# MCPS_Power_030414.net
KiCad netlist of a schematic drawn in Altium Designer
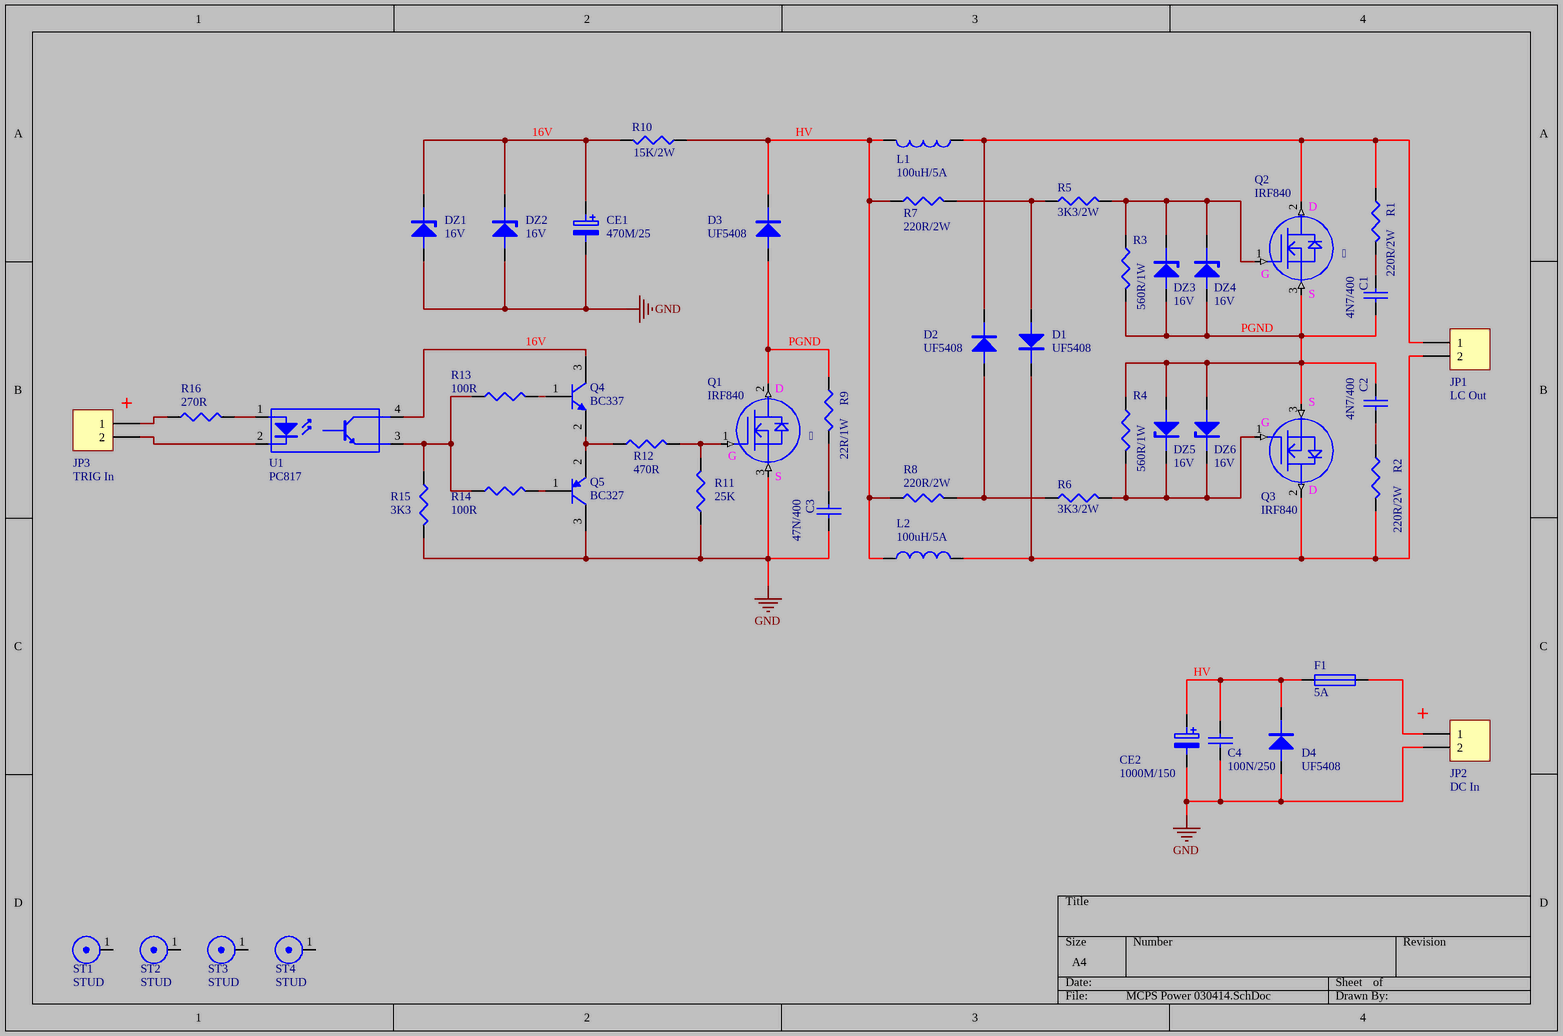
[diagram p0: MCPS Power 030414.SchDoc]

(export (version "E")
  (design (tool "Eeschema 10.0.6"))
  (components
    (comp (ref "C1") (value "4N7/400") (footprint "C3P") (libsource (lib "*") (part "C")))
    (comp (ref "C2") (value "4N7/400") (footprint "C3P") (libsource (lib "*") (part "C")))
    (comp (ref "C3") (value "47N/400") (footprint "C2P") (libsource (lib "*") (part "C")))
    (comp (ref "C4") (value "100N/250") (footprint "C4P") (libsource (lib "*") (part "C")))
    (comp (ref "CE1") (value "470M/25") (footprint "cap2p12") (libsource (lib "*") (part "E")))
    (comp (ref "CE2") (value "1000M/150") (footprint "CAP3P5") (libsource (lib "*") (part "E")))
    (comp (ref "D1") (value "UF5408") (footprint "D54") (libsource (lib "MyAltiumLib9702") (part "D")))
    (comp (ref "D2") (value "UF5408") (footprint "D54") (libsource (lib "MyAltiumLib9702") (part "D")))
    (comp (ref "D3") (value "UF5408") (footprint "D54") (libsource (lib "MyAltiumLib9702") (part "D")))
    (comp (ref "D4") (value "UF5408") (footprint "D54") (libsource (lib "MyAltiumLib9702") (part "D")))
    (comp (ref "DZ1") (value "16V") (footprint "D5P") (libsource (lib "MyAltiumLib9702") (part "DZ")))
    (comp (ref "DZ2") (value "16V") (footprint "D5P") (libsource (lib "MyAltiumLib9702") (part "DZ")))
    (comp (ref "DZ3") (value "16V") (footprint "D5P") (libsource (lib "MyAltiumLib9702") (part "DZ")))
    (comp (ref "DZ4") (value "16V") (footprint "D5P") (libsource (lib "MyAltiumLib9702") (part "DZ")))
    (comp (ref "DZ5") (value "16V") (footprint "D5P") (libsource (lib "MyAltiumLib9702") (part "DZ")))
    (comp (ref "DZ6") (value "16V") (footprint "D5P") (libsource (lib "MyAltiumLib9702") (part "DZ")))
    (comp (ref "F1") (value "5A") (footprint "FS") (libsource (lib "1402 Schlib 2020") (part "FUSE1")))
    (comp (ref "JP1")
      (value "LC Out")
      (footprint "DG55X2")
      (description "Header, 2-Pin")
      (fields (field (name "PUBLISHER") "Altium Limited"))
      (libsource (lib "Miscellaneous Connectors") (part "Header 2"))
    )
    (comp (ref "JP2")
      (value "DC In")
      (footprint "DG55X2")
      (description "Header, 2-Pin")
      (fields (field (name "PUBLISHER") "Altium Limited"))
      (libsource (lib "Miscellaneous Connectors") (part "Header 2"))
    )
    (comp (ref "JP3")
      (value "TRIG In")
      (footprint "DSIP2")
      (description "Header, 2-Pin")
      (fields (field (name "PUBLISHER") "Altium Limited"))
      (libsource (lib "") (part "Header 2_1"))
    )
    (comp (ref "L1") (value "100uH/5A") (footprint "Inductor3916") (libsource (lib "") (part "INDUCTOR_1")))
    (comp (ref "L2")
      (value "100uH/5A")
      (footprint "Inductor3916")
      (libsource (lib "MyAltiumLib9702") (part "INDUCTOR"))
    )
    (comp (ref "Q1")
      (value "")
      (footprint "TO247-MOSPIN")
      (libsource (lib "1402 Schlib 2020") (part "MOSFET N"))
    )
    (comp (ref "Q2")
      (value "")
      (footprint "TO247-MOSPIN")
      (libsource (lib "1402 Schlib 2020") (part "MOSFET N"))
    )
    (comp (ref "Q3")
      (value "IRF840")
      (footprint "TO247-MOSPIN")
      (libsource (lib "1402 Schlib 2020") (part "MOSFET N"))
    )
    (comp (ref "Q4")
      (value "BC337")
      (footprint "CBE-BC546")
      (libsource (lib "1402 Schlib 2020") (part "BC546"))
    )
    (comp (ref "Q5")
      (value "BC327")
      (footprint "CBE-BC546")
      (description "PNP")
      (fields (field (name "PUBLISHER") "Altium Limited"))
      (libsource (lib "1402 Schlib 2020") (part "M6"))
    )
    (comp (ref "R1") (value "220R/2W") (footprint "W2") (libsource (lib "*") (part "R")))
    (comp (ref "R2") (value "220R/2W") (footprint "W2") (libsource (lib "*") (part "R")))
    (comp (ref "R3") (value "560R/1W") (footprint "W1") (libsource (lib "*") (part "R")))
    (comp (ref "R4") (value "560R/1W") (footprint "W1") (libsource (lib "*") (part "R")))
    (comp (ref "R5") (value "3K3/2W") (footprint "W2") (libsource (lib "*") (part "R")))
    (comp (ref "R6") (value "3K3/2W") (footprint "W2") (libsource (lib "*") (part "R")))
    (comp (ref "R7") (value "220R/2W") (footprint "W2") (libsource (lib "*") (part "R")))
    (comp (ref "R8") (value "220R/2W") (footprint "W2") (libsource (lib "*") (part "R")))
    (comp (ref "R9") (value "22R/1W") (footprint "W1") (libsource (lib "*") (part "R")))
    (comp (ref "R10") (value "15K/2W") (footprint "W2") (libsource (lib "*") (part "R")))
    (comp (ref "R11") (value "25K") (footprint "W1/4") (libsource (lib "*") (part "R")))
    (comp (ref "R12") (value "470R") (footprint "W1/4") (libsource (lib "*") (part "R")))
    (comp (ref "R13") (value "100R") (footprint "W1/4") (libsource (lib "*") (part "R")))
    (comp (ref "R14") (value "100R") (footprint "W1/4") (libsource (lib "*") (part "R")))
    (comp (ref "R15") (value "3K3") (footprint "W1/4") (libsource (lib "*") (part "R")))
    (comp (ref "R16") (value "270R") (footprint "W1/4") (libsource (lib "*") (part "R")))
    (comp (ref "ST1") (value "STUD") (footprint "CORNER") (libsource (lib "1402 Schlib 2020") (part "STUD")))
    (comp (ref "ST2") (value "STUD") (footprint "CORNER") (libsource (lib "1402 Schlib 2020") (part "STUD")))
    (comp (ref "ST3") (value "STUD") (footprint "CORNER") (libsource (lib "1402 Schlib 2020") (part "STUD")))
    (comp (ref "ST4") (value "STUD") (footprint "CORNER") (libsource (lib "1402 Schlib 2020") (part "STUD")))
    (comp (ref "U1")
      (value "PC817")
      (footprint "DIP4")
      (libsource (lib "1402 Schlib 2020") (part "OPTODIP4"))
    )
  )
  (nets
    (net (code "1") (name "/16V") (class "Default")
      (node (ref "CE1") (pin "1") (pintype "passive"))
      (node (ref "DZ1") (pin "2") (pinfunction "K_2") (pintype "passive"))
      (node (ref "DZ2") (pin "2") (pinfunction "K_2") (pintype "passive"))
      (node (ref "Q4") (pin "3") (pinfunction "C_3") (pintype "passive"))
      (node (ref "R10") (pin "2") (pintype "passive"))
      (node (ref "U1") (pin "4") (pinfunction "C_4") (pintype "passive"))
    )
    (net (code "2") (name "/HV") (class "Default")
      (node (ref "C4") (pin "1") (pintype "passive"))
      (node (ref "CE2") (pin "1") (pintype "passive"))
      (node (ref "D3") (pin "2") (pinfunction "K_2") (pintype "passive"))
      (node (ref "D4") (pin "2") (pinfunction "K_2") (pintype "passive"))
      (node (ref "F1") (pin "1") (pintype "passive"))
      (node (ref "L1") (pin "1") (pinfunction "1_1") (pintype "passive"))
      (node (ref "L2") (pin "1") (pinfunction "1_1") (pintype "passive"))
      (node (ref "R10") (pin "1") (pintype "passive"))
      (node (ref "R7") (pin "1") (pintype "passive"))
      (node (ref "R8") (pin "1") (pintype "passive"))
    )
    (net (code "3") (name "/PGND") (class "Default")
      (node (ref "C1") (pin "2") (pintype "passive"))
      (node (ref "C2") (pin "2") (pintype "passive"))
      (node (ref "D3") (pin "1") (pinfunction "A_1") (pintype "passive"))
      (node (ref "DZ3") (pin "1") (pinfunction "A_1") (pintype "passive"))
      (node (ref "DZ4") (pin "1") (pinfunction "A_1") (pintype "passive"))
      (node (ref "DZ5") (pin "1") (pinfunction "A_1") (pintype "passive"))
      (node (ref "DZ6") (pin "1") (pinfunction "A_1") (pintype "passive"))
      (node (ref "Q1") (pin "2") (pinfunction "D_2") (pintype "output"))
      (node (ref "Q2") (pin "3") (pinfunction "S_3") (pintype "input"))
      (node (ref "Q3") (pin "3") (pinfunction "S_3") (pintype "input"))
      (node (ref "R3") (pin "2") (pintype "passive"))
      (node (ref "R4") (pin "1") (pintype "passive"))
      (node (ref "R9") (pin "1") (pintype "passive"))
    )
    (net (code "4") (name "GND") (class "Default")
      (node (ref "C3") (pin "2") (pintype "passive"))
      (node (ref "C4") (pin "2") (pintype "passive"))
      (node (ref "CE1") (pin "2") (pintype "passive"))
      (node (ref "CE2") (pin "2") (pintype "passive"))
      (node (ref "D4") (pin "1") (pinfunction "A_1") (pintype "passive"))
      (node (ref "DZ1") (pin "1") (pinfunction "A_1") (pintype "passive"))
      (node (ref "DZ2") (pin "1") (pinfunction "A_1") (pintype "passive"))
      (node (ref "JP2") (pin "2") (pinfunction "2_2") (pintype "passive"))
      (node (ref "Q1") (pin "3") (pinfunction "S_3") (pintype "input"))
      (node (ref "Q5") (pin "3") (pinfunction "C_3") (pintype "passive"))
      (node (ref "R11") (pin "1") (pintype "passive"))
      (node (ref "R15") (pin "2") (pintype "passive"))
    )
    (net (code "5") (name "Net-(C1-Pad1)") (class "Default")
      (node (ref "C1") (pin "1") (pintype "passive"))
      (node (ref "R1") (pin "2") (pintype "passive"))
    )
    (net (code "6") (name "Net-(C2-Pad1)") (class "Default")
      (node (ref "C2") (pin "1") (pintype "passive"))
      (node (ref "R2") (pin "2") (pintype "passive"))
    )
    (net (code "7") (name "Net-(C3-Pad1)") (class "Default")
      (node (ref "C3") (pin "1") (pintype "passive"))
      (node (ref "R9") (pin "2") (pintype "passive"))
    )
    (net (code "8") (name "Net-(D1-A)") (class "Default")
      (node (ref "D1") (pin "1") (pinfunction "A_1") (pintype "passive"))
      (node (ref "R5") (pin "1") (pintype "passive"))
      (node (ref "R7") (pin "2") (pintype "passive"))
    )
    (net (code "9") (name "Net-(D1-K)") (class "Default")
      (node (ref "D1") (pin "2") (pinfunction "K_2") (pintype "passive"))
      (node (ref "JP1") (pin "2") (pinfunction "2_2") (pintype "passive"))
      (node (ref "L2") (pin "2") (pinfunction "2_2") (pintype "passive"))
      (node (ref "Q3") (pin "2") (pinfunction "D_2") (pintype "output"))
      (node (ref "R2") (pin "1") (pintype "passive"))
    )
    (net (code "10") (name "Net-(D2-A)") (class "Default")
      (node (ref "D2") (pin "1") (pinfunction "A_1") (pintype "passive"))
      (node (ref "R6") (pin "1") (pintype "passive"))
      (node (ref "R8") (pin "2") (pintype "passive"))
    )
    (net (code "11") (name "Net-(D2-K)") (class "Default")
      (node (ref "D2") (pin "2") (pinfunction "K_2") (pintype "passive"))
      (node (ref "JP1") (pin "1") (pinfunction "1_1") (pintype "passive"))
      (node (ref "L1") (pin "2") (pinfunction "2_2") (pintype "passive"))
      (node (ref "Q2") (pin "2") (pinfunction "D_2") (pintype "output"))
      (node (ref "R1") (pin "1") (pintype "passive"))
    )
    (net (code "12") (name "Net-(DZ3-K)") (class "Default")
      (node (ref "DZ3") (pin "2") (pinfunction "K_2") (pintype "passive"))
      (node (ref "DZ4") (pin "2") (pinfunction "K_2") (pintype "passive"))
      (node (ref "Q2") (pin "1") (pinfunction "G_1") (pintype "input"))
      (node (ref "R3") (pin "1") (pintype "passive"))
      (node (ref "R5") (pin "2") (pintype "passive"))
    )
    (net (code "13") (name "Net-(DZ5-K)") (class "Default")
      (node (ref "DZ5") (pin "2") (pinfunction "K_2") (pintype "passive"))
      (node (ref "DZ6") (pin "2") (pinfunction "K_2") (pintype "passive"))
      (node (ref "Q3") (pin "1") (pinfunction "G_1") (pintype "input"))
      (node (ref "R4") (pin "2") (pintype "passive"))
      (node (ref "R6") (pin "2") (pintype "passive"))
    )
    (net (code "14") (name "Net-(F1-Pad2)") (class "Default")
      (node (ref "F1") (pin "2") (pintype "passive"))
      (node (ref "JP2") (pin "1") (pinfunction "1_1") (pintype "passive"))
    )
    (net (code "15") (name "Net-(JP3-Pad1)") (class "Default")
      (node (ref "JP3") (pin "1") (pinfunction "1_1") (pintype "passive"))
      (node (ref "R16") (pin "1") (pintype "passive"))
    )
    (net (code "16") (name "Net-(Q1-G)") (class "Default")
      (node (ref "Q1") (pin "1") (pinfunction "G_1") (pintype "input"))
      (node (ref "R11") (pin "2") (pintype "passive"))
      (node (ref "R12") (pin "2") (pintype "passive"))
    )
    (net (code "17") (name "Net-(Q4-B)") (class "Default")
      (node (ref "Q4") (pin "1") (pinfunction "B_1") (pintype "passive"))
      (node (ref "R13") (pin "2") (pintype "passive"))
    )
    (net (code "18") (name "Net-(Q4-E)") (class "Default")
      (node (ref "Q4") (pin "2") (pinfunction "E_2") (pintype "passive"))
      (node (ref "Q5") (pin "2") (pinfunction "B_2") (pintype "passive"))
      (node (ref "R12") (pin "1") (pintype "passive"))
    )
    (net (code "19") (name "Net-(Q5-E)") (class "Default")
      (node (ref "Q5") (pin "1") (pinfunction "E_1") (pintype "passive"))
      (node (ref "R14") (pin "2") (pintype "passive"))
    )
    (net (code "20") (name "Net-(U1-A)") (class "Default")
      (node (ref "R16") (pin "2") (pintype "passive"))
      (node (ref "U1") (pin "1") (pinfunction "A_1") (pintype "passive"))
    )
    (net (code "21") (name "Net-(U1-E)") (class "Default")
      (node (ref "R13") (pin "1") (pintype "passive"))
      (node (ref "R14") (pin "1") (pintype "passive"))
      (node (ref "R15") (pin "1") (pintype "passive"))
      (node (ref "U1") (pin "3") (pinfunction "E_3") (pintype "passive"))
    )
    (net (code "22") (name "Net-(U1-K)") (class "Default")
      (node (ref "JP3") (pin "2") (pinfunction "2_2") (pintype "passive"))
      (node (ref "U1") (pin "2") (pinfunction "K_2") (pintype "passive"))
    )
    (net (code "23") (name "unconnected-(ST1-Pad1)") (class "Default")
      (node (ref "ST1") (pin "1") (pintype "passive"))
    )
    (net (code "24") (name "unconnected-(ST2-Pad1)") (class "Default")
      (node (ref "ST2") (pin "1") (pintype "passive"))
    )
    (net (code "25") (name "unconnected-(ST3-Pad1)") (class "Default")
      (node (ref "ST3") (pin "1") (pintype "passive"))
    )
    (net (code "26") (name "unconnected-(ST4-Pad1)") (class "Default")
      (node (ref "ST4") (pin "1") (pintype "passive"))
    )
  )
)
